# waterLEDSheet.net
KiCad netlist of a schematic drawn in Altium Designer
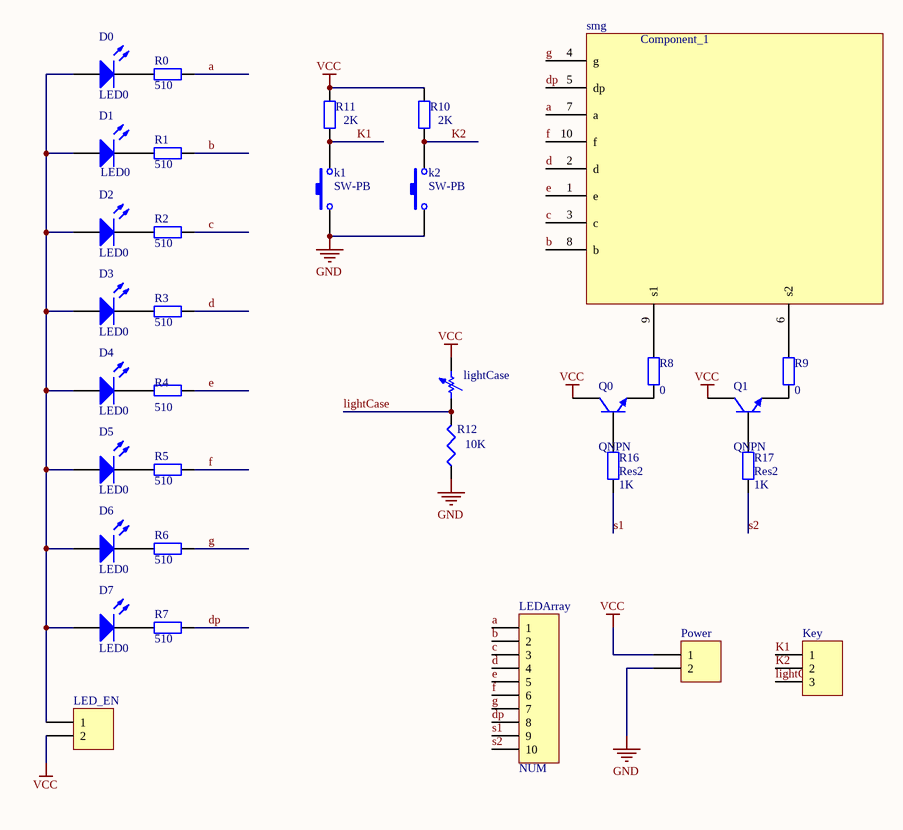
[diagram p0: waterLEDSheet.SchDoc]

(export (version "E")
  (design (tool "Eeschema 10.0.6"))
  (components
    (comp (ref "D0")
      (value "LED0")
      (footprint "C1210_M")
      (description "Typical INFRARED GaAs LED")
      (fields (field (name "PUBLISHER") "Altium Limited"))
      (libsource (lib "Miscellaneous Devices") (part "LED0"))
    )
    (comp (ref "D1")
      (value "LED0")
      (footprint "C1210_M")
      (description "Typical INFRARED GaAs LED")
      (fields (field (name "PUBLISHER") "Altium Limited"))
      (libsource (lib "Miscellaneous Devices") (part "LED0"))
    )
    (comp (ref "D2")
      (value "LED0")
      (footprint "C1210_M")
      (description "Typical INFRARED GaAs LED")
      (fields (field (name "PUBLISHER") "Altium Limited"))
      (libsource (lib "Miscellaneous Devices") (part "LED0"))
    )
    (comp (ref "D3")
      (value "LED0")
      (footprint "C1210_M")
      (description "Typical INFRARED GaAs LED")
      (fields (field (name "PUBLISHER") "Altium Limited"))
      (libsource (lib "Miscellaneous Devices") (part "LED0"))
    )
    (comp (ref "D4")
      (value "LED0")
      (footprint "C1210_M")
      (description "Typical INFRARED GaAs LED")
      (fields (field (name "PUBLISHER") "Altium Limited"))
      (libsource (lib "Miscellaneous Devices") (part "LED0"))
    )
    (comp (ref "D5")
      (value "LED0")
      (footprint "C1210_M")
      (description "Typical INFRARED GaAs LED")
      (fields (field (name "PUBLISHER") "Altium Limited"))
      (libsource (lib "Miscellaneous Devices") (part "LED0"))
    )
    (comp (ref "D6")
      (value "LED0")
      (footprint "C1210_M")
      (description "Typical INFRARED GaAs LED")
      (fields (field (name "PUBLISHER") "Altium Limited"))
      (libsource (lib "Miscellaneous Devices") (part "LED0"))
    )
    (comp (ref "D7")
      (value "LED0")
      (footprint "C1210_M")
      (description "Typical INFRARED GaAs LED")
      (fields (field (name "PUBLISHER") "Altium Limited"))
      (libsource (lib "Miscellaneous Devices") (part "LED0"))
    )
    (comp (ref "k1")
      (value "SW-PB")
      (footprint "KEY_SODFL_2-Leads")
      (description "Switch")
      (fields (field (name "PUBLISHER") "Altium Limited"))
      (libsource (lib "Miscellaneous Devices") (part "SW-PB"))
    )
    (comp (ref "k2")
      (value "SW-PB")
      (footprint "KEY_SODFL_2-Leads")
      (description "Switch")
      (fields (field (name "PUBLISHER") "Altium Limited"))
      (libsource (lib "Miscellaneous Devices") (part "SW-PB"))
    )
    (comp (ref "Key")
      (value "~")
      (footprint "HDR1X3")
      (description "Header, 3-Pin")
      (fields (field (name "PUBLISHER") "Altium Limited"))
      (libsource (lib "Miscellaneous Connectors") (part "Header 3"))
    )
    (comp (ref "LEDArray")
      (value "NUM")
      (footprint "HDR1X10")
      (description "Header, 10-Pin")
      (fields (field (name "PUBLISHER") "Altium Limited"))
      (libsource (lib "Miscellaneous Connectors") (part "Header 10"))
    )
    (comp (ref "LED_EN")
      (value "~")
      (footprint "HDR1X2")
      (description "Header, 2-Pin")
      (fields (field (name "PUBLISHER") "Altium Limited"))
      (libsource (lib "Miscellaneous Connectors") (part "Header 2"))
    )
    (comp (ref "lightCase")
      (value "~")
      (footprint "RAD-0.2")
      (description "Variable Resistor")
      (fields (field (name "PUBLISHER") "Altium Limited"))
      (libsource (lib "Miscellaneous Devices") (part "Res Adj1"))
    )
    (comp (ref "Power")
      (value "Header 2")
      (footprint "HDR1X2")
      (description "Header, 2-Pin")
      (fields (field (name "PUBLISHER") "Altium Limited"))
      (libsource (lib "Miscellaneous Connectors") (part "Header 2"))
    )
    (comp (ref "Q0")
      (value "QNPN")
      (footprint "SOT23_M")
      (description "NPN Bipolar Transistor")
      (fields (field (name "PUBLISHER") "Altium Limited"))
      (libsource (lib "Miscellaneous Devices") (part "QNPN"))
    )
    (comp (ref "Q1")
      (value "QNPN")
      (footprint "SOT23_M")
      (description "NPN Bipolar Transistor")
      (fields (field (name "PUBLISHER") "Altium Limited"))
      (libsource (lib "Miscellaneous Devices") (part "QNPN"))
    )
    (comp (ref "R0")
      (value "510")
      (footprint "6-0805_N")
      (description "Resistor")
      (fields (field (name "PUBLISHER") "Altium Limited"))
      (libsource (lib "Miscellaneous Devices") (part "Res2"))
    )
    (comp (ref "R1")
      (value "510")
      (footprint "6-0805_N")
      (description "Resistor")
      (fields (field (name "PUBLISHER") "Altium Limited"))
      (libsource (lib "Miscellaneous Devices") (part "Res2"))
    )
    (comp (ref "R2")
      (value "510")
      (footprint "6-0805_N")
      (description "Resistor")
      (fields (field (name "PUBLISHER") "Altium Limited"))
      (libsource (lib "Miscellaneous Devices") (part "Res2"))
    )
    (comp (ref "R3")
      (value "510")
      (footprint "6-0805_N")
      (description "Resistor")
      (fields (field (name "PUBLISHER") "Altium Limited"))
      (libsource (lib "Miscellaneous Devices") (part "Res2"))
    )
    (comp (ref "R4")
      (value "510")
      (footprint "6-0805_N")
      (description "Resistor")
      (fields (field (name "PUBLISHER") "Altium Limited"))
      (libsource (lib "Miscellaneous Devices") (part "Res2"))
    )
    (comp (ref "R5")
      (value "510")
      (footprint "6-0805_N")
      (description "Resistor")
      (fields (field (name "PUBLISHER") "Altium Limited"))
      (libsource (lib "Miscellaneous Devices") (part "Res2"))
    )
    (comp (ref "R6")
      (value "510")
      (footprint "6-0805_N")
      (description "Resistor")
      (fields (field (name "PUBLISHER") "Altium Limited"))
      (libsource (lib "Miscellaneous Devices") (part "Res2"))
    )
    (comp (ref "R7")
      (value "510")
      (footprint "6-0805_N")
      (description "Resistor")
      (fields (field (name "PUBLISHER") "Altium Limited"))
      (libsource (lib "Miscellaneous Devices") (part "Res2"))
    )
    (comp (ref "R8")
      (value "0")
      (footprint "6-0805_N")
      (description "Resistor")
      (fields (field (name "PUBLISHER") "Altium Limited"))
      (libsource (lib "") (part "Res2_1"))
    )
    (comp (ref "R9")
      (value "0")
      (footprint "6-0805_N")
      (description "Resistor")
      (fields (field (name "PUBLISHER") "Altium Limited"))
      (libsource (lib "") (part "Res2_1"))
    )
    (comp (ref "R10")
      (value "2K")
      (footprint "6-0805_N")
      (description "Resistor")
      (fields (field (name "PUBLISHER") "Altium Limited"))
      (libsource (lib "") (part "Res2_2"))
    )
    (comp (ref "R11")
      (value "2K")
      (footprint "6-0805_N")
      (description "Resistor")
      (fields (field (name "PUBLISHER") "Altium Limited"))
      (libsource (lib "") (part "Res2_1"))
    )
    (comp (ref "R12")
      (value "10K")
      (footprint "6-0805_N")
      (description "Resistor")
      (fields (field (name "Comment") "Res3") (field (name "PUBLISHER") "Altium Limited"))
      (libsource (lib "Miscellaneous Devices") (part "Res3"))
    )
    (comp (ref "R16")
      (value "Res2")
      (footprint "6-0805_N")
      (description "Resistor")
      (fields (field (name "ALTIUM_VALUE") "1K") (field (name "PUBLISHER") "Altium Limited"))
      (libsource (lib "") (part "Res2_1"))
    )
    (comp (ref "R17")
      (value "Res2")
      (footprint "6-0805_N")
      (description "Resistor")
      (fields (field (name "ALTIUM_VALUE") "1K") (field (name "PUBLISHER") "Altium Limited"))
      (libsource (lib "") (part "Res2_1"))
    )
    (comp (ref "smg")
      (value "Component_1")
      (footprint "Nixie_light")
      (libsource (lib "smg") (part "Component_1"))
    )
  )
  (nets
    (net (code "1") (name "/K1") (class "Default")
      (node (ref "Key") (pin "1") (pinfunction "1_1") (pintype "passive"))
      (node (ref "R11") (pin "1") (pinfunction "1_1") (pintype "passive"))
      (node (ref "k1") (pin "2") (pinfunction "2_2") (pintype "passive"))
    )
    (net (code "2") (name "/K2") (class "Default")
      (node (ref "Key") (pin "2") (pinfunction "2_2") (pintype "passive"))
      (node (ref "R10") (pin "2") (pinfunction "2_2") (pintype "passive"))
      (node (ref "k2") (pin "2") (pinfunction "2_2") (pintype "passive"))
    )
    (net (code "3") (name "/a") (class "Default")
      (node (ref "LEDArray") (pin "1") (pinfunction "1_1") (pintype "passive"))
      (node (ref "R0") (pin "2") (pinfunction "2_2") (pintype "passive"))
      (node (ref "smg") (pin "7") (pinfunction "a_7") (pintype "passive"))
    )
    (net (code "4") (name "/b") (class "Default")
      (node (ref "LEDArray") (pin "2") (pinfunction "2_2") (pintype "passive"))
      (node (ref "R1") (pin "2") (pinfunction "2_2") (pintype "passive"))
      (node (ref "smg") (pin "8") (pinfunction "b_8") (pintype "passive"))
    )
    (net (code "5") (name "/c") (class "Default")
      (node (ref "LEDArray") (pin "3") (pinfunction "3_3") (pintype "passive"))
      (node (ref "R2") (pin "2") (pinfunction "2_2") (pintype "passive"))
      (node (ref "smg") (pin "3") (pinfunction "c_3") (pintype "passive"))
    )
    (net (code "6") (name "/d") (class "Default")
      (node (ref "LEDArray") (pin "4") (pinfunction "4_4") (pintype "passive"))
      (node (ref "R3") (pin "2") (pinfunction "2_2") (pintype "passive"))
      (node (ref "smg") (pin "2") (pinfunction "d_2") (pintype "passive"))
    )
    (net (code "7") (name "/dp") (class "Default")
      (node (ref "LEDArray") (pin "8") (pinfunction "8_8") (pintype "passive"))
      (node (ref "R7") (pin "2") (pinfunction "2_2") (pintype "passive"))
      (node (ref "smg") (pin "5") (pinfunction "dp_5") (pintype "passive"))
    )
    (net (code "8") (name "/e") (class "Default")
      (node (ref "LEDArray") (pin "5") (pinfunction "5_5") (pintype "passive"))
      (node (ref "R4") (pin "2") (pinfunction "2_2") (pintype "passive"))
      (node (ref "smg") (pin "1") (pinfunction "e_1") (pintype "passive"))
    )
    (net (code "9") (name "/f") (class "Default")
      (node (ref "LEDArray") (pin "6") (pinfunction "6_6") (pintype "passive"))
      (node (ref "R5") (pin "2") (pinfunction "2_2") (pintype "passive"))
      (node (ref "smg") (pin "10") (pinfunction "f_10") (pintype "passive"))
    )
    (net (code "10") (name "/g") (class "Default")
      (node (ref "LEDArray") (pin "7") (pinfunction "7_7") (pintype "passive"))
      (node (ref "R6") (pin "2") (pinfunction "2_2") (pintype "passive"))
      (node (ref "smg") (pin "4") (pinfunction "g_4") (pintype "passive"))
    )
    (net (code "11") (name "/lightCase") (class "Default")
      (node (ref "Key") (pin "3") (pinfunction "3_3") (pintype "passive"))
      (node (ref "R12") (pin "2") (pinfunction "2_2") (pintype "passive"))
      (node (ref "lightCase") (pin "1") (pinfunction "1_1") (pintype "passive"))
    )
    (net (code "12") (name "/s1") (class "Default")
      (node (ref "LEDArray") (pin "9") (pinfunction "9_9") (pintype "passive"))
      (node (ref "R16") (pin "1") (pinfunction "1_1") (pintype "passive"))
    )
    (net (code "13") (name "/s2") (class "Default")
      (node (ref "LEDArray") (pin "10") (pinfunction "10_10") (pintype "passive"))
      (node (ref "R17") (pin "1") (pinfunction "1_1") (pintype "passive"))
    )
    (net (code "14") (name "GND") (class "Default")
      (node (ref "Power") (pin "2") (pinfunction "2_2") (pintype "passive"))
      (node (ref "R12") (pin "1") (pinfunction "1_1") (pintype "passive"))
      (node (ref "k1") (pin "1") (pinfunction "1_1") (pintype "passive"))
      (node (ref "k2") (pin "1") (pinfunction "1_1") (pintype "passive"))
    )
    (net (code "15") (name "Net-(D0-A)") (class "Default")
      (node (ref "D0") (pin "1") (pinfunction "A_1") (pintype "passive"))
      (node (ref "D1") (pin "1") (pinfunction "A_1") (pintype "passive"))
      (node (ref "D2") (pin "1") (pinfunction "A_1") (pintype "passive"))
      (node (ref "D3") (pin "1") (pinfunction "A_1") (pintype "passive"))
      (node (ref "D4") (pin "1") (pinfunction "A_1") (pintype "passive"))
      (node (ref "D5") (pin "1") (pinfunction "A_1") (pintype "passive"))
      (node (ref "D6") (pin "1") (pinfunction "A_1") (pintype "passive"))
      (node (ref "D7") (pin "1") (pinfunction "A_1") (pintype "passive"))
      (node (ref "LED_EN") (pin "1") (pinfunction "1_1") (pintype "passive"))
    )
    (net (code "16") (name "Net-(D0-K)") (class "Default")
      (node (ref "D0") (pin "2") (pinfunction "K_2") (pintype "passive"))
      (node (ref "R0") (pin "1") (pinfunction "1_1") (pintype "passive"))
    )
    (net (code "17") (name "Net-(D1-K)") (class "Default")
      (node (ref "D1") (pin "2") (pinfunction "K_2") (pintype "passive"))
      (node (ref "R1") (pin "1") (pinfunction "1_1") (pintype "passive"))
    )
    (net (code "18") (name "Net-(D2-K)") (class "Default")
      (node (ref "D2") (pin "2") (pinfunction "K_2") (pintype "passive"))
      (node (ref "R2") (pin "1") (pinfunction "1_1") (pintype "passive"))
    )
    (net (code "19") (name "Net-(D3-K)") (class "Default")
      (node (ref "D3") (pin "2") (pinfunction "K_2") (pintype "passive"))
      (node (ref "R3") (pin "1") (pinfunction "1_1") (pintype "passive"))
    )
    (net (code "20") (name "Net-(D4-K)") (class "Default")
      (node (ref "D4") (pin "2") (pinfunction "K_2") (pintype "passive"))
      (node (ref "R4") (pin "1") (pinfunction "1_1") (pintype "passive"))
    )
    (net (code "21") (name "Net-(D5-K)") (class "Default")
      (node (ref "D5") (pin "2") (pinfunction "K_2") (pintype "passive"))
      (node (ref "R5") (pin "1") (pinfunction "1_1") (pintype "passive"))
    )
    (net (code "22") (name "Net-(D6-K)") (class "Default")
      (node (ref "D6") (pin "2") (pinfunction "K_2") (pintype "passive"))
      (node (ref "R6") (pin "1") (pinfunction "1_1") (pintype "passive"))
    )
    (net (code "23") (name "Net-(D7-K)") (class "Default")
      (node (ref "D7") (pin "2") (pinfunction "K_2") (pintype "passive"))
      (node (ref "R7") (pin "1") (pinfunction "1_1") (pintype "passive"))
    )
    (net (code "24") (name "Net-(Q0-B)") (class "Default")
      (node (ref "Q0") (pin "2") (pinfunction "B_2") (pintype "passive"))
      (node (ref "R16") (pin "2") (pinfunction "2_2") (pintype "passive"))
    )
    (net (code "25") (name "Net-(Q0-E)") (class "Default")
      (node (ref "Q0") (pin "3") (pinfunction "E_3") (pintype "passive"))
      (node (ref "R8") (pin "1") (pinfunction "1_1") (pintype "passive"))
    )
    (net (code "26") (name "Net-(Q1-B)") (class "Default")
      (node (ref "Q1") (pin "2") (pinfunction "B_2") (pintype "passive"))
      (node (ref "R17") (pin "2") (pinfunction "2_2") (pintype "passive"))
    )
    (net (code "27") (name "Net-(Q1-E)") (class "Default")
      (node (ref "Q1") (pin "3") (pinfunction "E_3") (pintype "passive"))
      (node (ref "R9") (pin "1") (pinfunction "1_1") (pintype "passive"))
    )
    (net (code "28") (name "Net-(smg-s1)") (class "Default")
      (node (ref "R8") (pin "2") (pinfunction "2_2") (pintype "passive"))
      (node (ref "smg") (pin "9") (pinfunction "s1_9") (pintype "passive"))
    )
    (net (code "29") (name "Net-(smg-s2)") (class "Default")
      (node (ref "R9") (pin "2") (pinfunction "2_2") (pintype "passive"))
      (node (ref "smg") (pin "6") (pinfunction "s2_6") (pintype "passive"))
    )
    (net (code "30") (name "VCC") (class "Default")
      (node (ref "LED_EN") (pin "2") (pinfunction "2_2") (pintype "passive"))
      (node (ref "Power") (pin "1") (pinfunction "1_1") (pintype "passive"))
      (node (ref "Q0") (pin "1") (pinfunction "C_1") (pintype "passive"))
      (node (ref "Q1") (pin "1") (pinfunction "C_1") (pintype "passive"))
      (node (ref "R10") (pin "1") (pinfunction "1_1") (pintype "passive"))
      (node (ref "R11") (pin "2") (pinfunction "2_2") (pintype "passive"))
      (node (ref "lightCase") (pin "2") (pinfunction "2_2") (pintype "passive"))
    )
  )
)
